# D_class_amplifier_schematic.net
KiCad netlist of a schematic drawn in Altium Designer
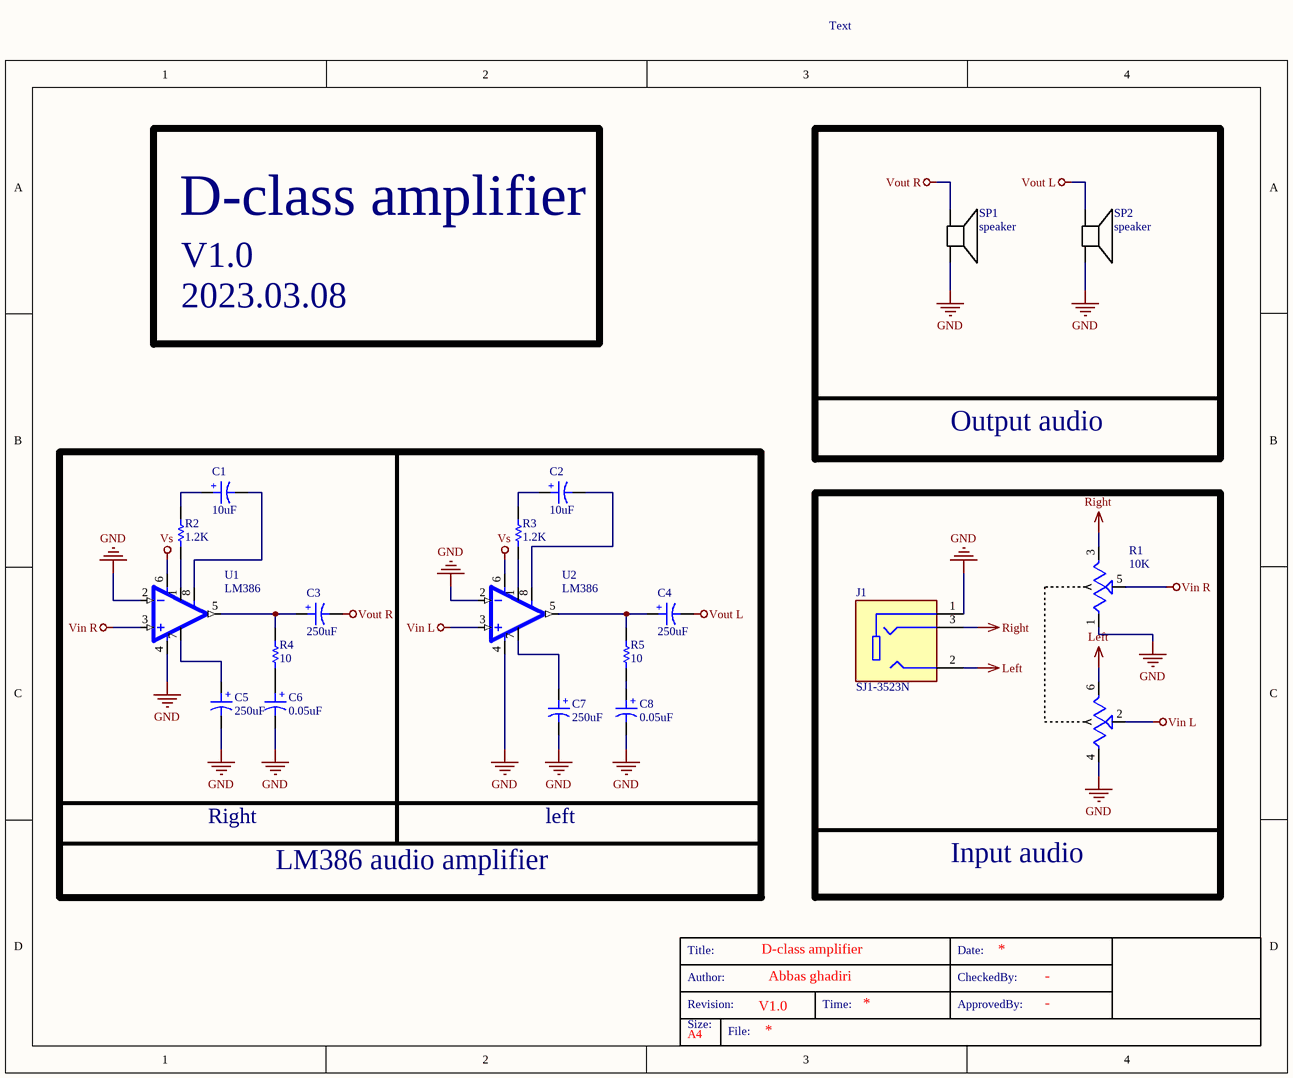
[diagram p0: D_class_amplifier_schematic.SchDoc]

(export (version "E")
  (design (tool "Eeschema 10.0.6"))
  (components
    (comp (ref "C1")
      (value "10uF")
      (footprint "personal_library:capacity")
      (description "Cap electrolitic radial 6x7-2.5")
      (libsource (lib "personal_library") (part "Cap electrolitic radial 6x7-2.5"))
    )
    (comp (ref "C2")
      (value "10uF")
      (footprint "personal_library:capacity")
      (description "Cap electrolitic radial 6x7-2.5")
      (libsource (lib "personal_library") (part "Cap electrolitic radial 6x7-2.5"))
    )
    (comp (ref "C3")
      (value "250uF")
      (footprint "personal_library:capacity")
      (description "Cap electrolitic radial 6x7-2.5")
      (libsource (lib "personal_library") (part "Cap electrolitic radial 6x7-2.5"))
    )
    (comp (ref "C4")
      (value "250uF")
      (footprint "personal_library:capacity")
      (description "Cap electrolitic radial 6x7-2.5")
      (libsource (lib "personal_library") (part "Cap electrolitic radial 6x7-2.5"))
    )
    (comp (ref "C5")
      (value "250uF")
      (footprint "personal_library:capacity")
      (description "Cap electrolitic radial 6x7-2.5")
      (libsource (lib "personal_library") (part "Cap electrolitic radial 6x7-2.5"))
    )
    (comp (ref "C6")
      (value "0.05uF")
      (footprint "personal_library:capacity")
      (description "Cap electrolitic radial 6x7-2.5")
      (libsource (lib "personal_library") (part "Cap electrolitic radial 6x7-2.5"))
    )
    (comp (ref "C7")
      (value "250uF")
      (footprint "personal_library:capacity")
      (description "Cap electrolitic radial 6x7-2.5")
      (libsource (lib "personal_library") (part "Cap electrolitic radial 6x7-2.5"))
    )
    (comp (ref "C8")
      (value "0.05uF")
      (footprint "personal_library:capacity")
      (description "Cap electrolitic radial 6x7-2.5")
      (libsource (lib "personal_library") (part "Cap electrolitic radial 6x7-2.5"))
    )
    (comp (ref "J1")
      (value "SJ1-3523N")
      (footprint "personal_library:SJ1-3523N")
      (libsource (lib "personal_library") (part "SJ1-3523N"))
    )
    (comp (ref "R1")
      (value "10K")
      (footprint "personal_library:PTV112-4")
      (libsource (lib "personal_library") (part "PTV112-4"))
    )
    (comp (ref "R2")
      (value "1.2K")
      (footprint "personal_library:resistor 1206")
      (libsource (lib "personal_library") (part "Resistor 1206"))
    )
    (comp (ref "R3")
      (value "1.2K")
      (footprint "personal_library:resistor 1206")
      (libsource (lib "personal_library") (part "Resistor 1206"))
    )
    (comp (ref "R4")
      (value "10")
      (footprint "personal_library:resistor 1206")
      (libsource (lib "personal_library") (part "Resistor 1206"))
    )
    (comp (ref "R5")
      (value "10")
      (footprint "personal_library:resistor 1206")
      (libsource (lib "personal_library") (part "Resistor 1206"))
    )
    (comp (ref "SP1")
      (value "speaker")
      (footprint "personal_library:speaker")
      (libsource (lib "personal_library") (part "speaker"))
    )
    (comp (ref "SP2")
      (value "speaker")
      (footprint "personal_library:speaker")
      (libsource (lib "personal_library") (part "speaker"))
    )
    (comp (ref "U1")
      (value "LM386")
      (footprint "personal_library:LM386")
      (libsource (lib "personal_library") (part "LM386"))
    )
    (comp (ref "U2")
      (value "LM386")
      (footprint "personal_library:LM386")
      (libsource (lib "personal_library") (part "LM386"))
    )
  )
  (nets
    (net (code "1") (name "GND") (class "Default")
      (node (ref "C5") (pin "2") (pinfunction "2_2") (pintype "passive"))
      (node (ref "C6") (pin "2") (pinfunction "2_2") (pintype "passive"))
      (node (ref "C7") (pin "2") (pinfunction "2_2") (pintype "passive"))
      (node (ref "C8") (pin "2") (pinfunction "2_2") (pintype "passive"))
      (node (ref "J1") (pin "1") (pinfunction "1_1") (pintype "passive"))
      (node (ref "R1") (pin "1") (pinfunction "1_1") (pintype "passive"))
      (node (ref "R1") (pin "4") (pinfunction "1_4") (pintype "passive"))
      (node (ref "SP1") (pin "2") (pinfunction "NEG_2") (pintype "passive"))
      (node (ref "SP2") (pin "2") (pinfunction "NEG_2") (pintype "passive"))
      (node (ref "U1") (pin "2") (pinfunction "-IN_2") (pintype "input"))
      (node (ref "U1") (pin "4") (pinfunction "V-_4") (pintype "power_in"))
      (node (ref "U2") (pin "2") (pinfunction "-IN_2") (pintype "input"))
      (node (ref "U2") (pin "4") (pinfunction "V-_4") (pintype "power_in"))
    )
    (net (code "2") (name "Left") (class "Default")
      (node (ref "J1") (pin "2") (pinfunction "2_2") (pintype "passive"))
      (node (ref "R1") (pin "6") (pinfunction "3_6") (pintype "passive"))
    )
    (net (code "3") (name "Net-(C1-Pad1)") (class "Default")
      (node (ref "C1") (pin "1") (pinfunction "1_1") (pintype "passive"))
      (node (ref "R2") (pin "2") (pinfunction "2_2") (pintype "passive"))
    )
    (net (code "4") (name "Net-(C2-Pad1)") (class "Default")
      (node (ref "C2") (pin "1") (pinfunction "1_1") (pintype "passive"))
      (node (ref "R3") (pin "2") (pinfunction "2_2") (pintype "passive"))
    )
    (net (code "5") (name "Net-(C6-Pad1)") (class "Default")
      (node (ref "C6") (pin "1") (pinfunction "1_1") (pintype "passive"))
      (node (ref "R4") (pin "1") (pinfunction "1_1") (pintype "passive"))
    )
    (net (code "6") (name "Net-(C8-Pad1)") (class "Default")
      (node (ref "C8") (pin "1") (pinfunction "1_1") (pintype "passive"))
      (node (ref "R5") (pin "1") (pinfunction "1_1") (pintype "passive"))
    )
    (net (code "7") (name "Net-(U1-BP)") (class "Default")
      (node (ref "C5") (pin "1") (pinfunction "1_1") (pintype "passive"))
      (node (ref "U1") (pin "7") (pinfunction "BP_7") (pintype "bidirectional"))
    )
    (net (code "8") (name "Net-(U1-GAIN@1)") (class "Default")
      (node (ref "R2") (pin "1") (pinfunction "1_1") (pintype "passive"))
      (node (ref "U1") (pin "1") (pinfunction "GAIN@1_1") (pintype "bidirectional"))
    )
    (net (code "9") (name "Net-(U1-GAIN@8)") (class "Default")
      (node (ref "C1") (pin "2") (pinfunction "2_2") (pintype "passive"))
      (node (ref "U1") (pin "8") (pinfunction "GAIN@8_8") (pintype "bidirectional"))
    )
    (net (code "10") (name "Net-(U1-OUT)") (class "Default")
      (node (ref "C3") (pin "1") (pinfunction "1_1") (pintype "passive"))
      (node (ref "R4") (pin "2") (pinfunction "2_2") (pintype "passive"))
      (node (ref "U1") (pin "5") (pinfunction "OUT_5") (pintype "output"))
    )
    (net (code "11") (name "Net-(U2-BP)") (class "Default")
      (node (ref "C7") (pin "1") (pinfunction "1_1") (pintype "passive"))
      (node (ref "U2") (pin "7") (pinfunction "BP_7") (pintype "bidirectional"))
    )
    (net (code "12") (name "Net-(U2-GAIN@1)") (class "Default")
      (node (ref "R3") (pin "1") (pinfunction "1_1") (pintype "passive"))
      (node (ref "U2") (pin "1") (pinfunction "GAIN@1_1") (pintype "bidirectional"))
    )
    (net (code "13") (name "Net-(U2-GAIN@8)") (class "Default")
      (node (ref "C2") (pin "2") (pinfunction "2_2") (pintype "passive"))
      (node (ref "U2") (pin "8") (pinfunction "GAIN@8_8") (pintype "bidirectional"))
    )
    (net (code "14") (name "Net-(U2-OUT)") (class "Default")
      (node (ref "C4") (pin "1") (pinfunction "1_1") (pintype "passive"))
      (node (ref "R5") (pin "2") (pinfunction "2_2") (pintype "passive"))
      (node (ref "U2") (pin "5") (pinfunction "OUT_5") (pintype "output"))
    )
    (net (code "15") (name "Right") (class "Default")
      (node (ref "J1") (pin "3") (pinfunction "3_3") (pintype "passive"))
      (node (ref "R1") (pin "3") (pinfunction "3_3") (pintype "passive"))
    )
    (net (code "16") (name "Vin L") (class "Default")
      (node (ref "R1") (pin "2") (pinfunction "2_2") (pintype "passive"))
      (node (ref "U2") (pin "3") (pinfunction "+IN_3") (pintype "input"))
    )
    (net (code "17") (name "Vin R") (class "Default")
      (node (ref "R1") (pin "5") (pinfunction "2_5") (pintype "passive"))
      (node (ref "U1") (pin "3") (pinfunction "+IN_3") (pintype "input"))
    )
    (net (code "18") (name "Vout L") (class "Default")
      (node (ref "C4") (pin "2") (pinfunction "2_2") (pintype "passive"))
      (node (ref "SP2") (pin "1") (pinfunction "POS_1") (pintype "passive"))
    )
    (net (code "19") (name "Vout R") (class "Default")
      (node (ref "C3") (pin "2") (pinfunction "2_2") (pintype "passive"))
      (node (ref "SP1") (pin "1") (pinfunction "POS_1") (pintype "passive"))
    )
    (net (code "20") (name "Vs") (class "Default")
      (node (ref "U1") (pin "6") (pinfunction "V+_6") (pintype "power_in"))
      (node (ref "U2") (pin "6") (pinfunction "V+_6") (pintype "power_in"))
    )
  )
)
